# LED_Driver_-_4.net
KiCad netlist of a schematic drawn in Altium Designer
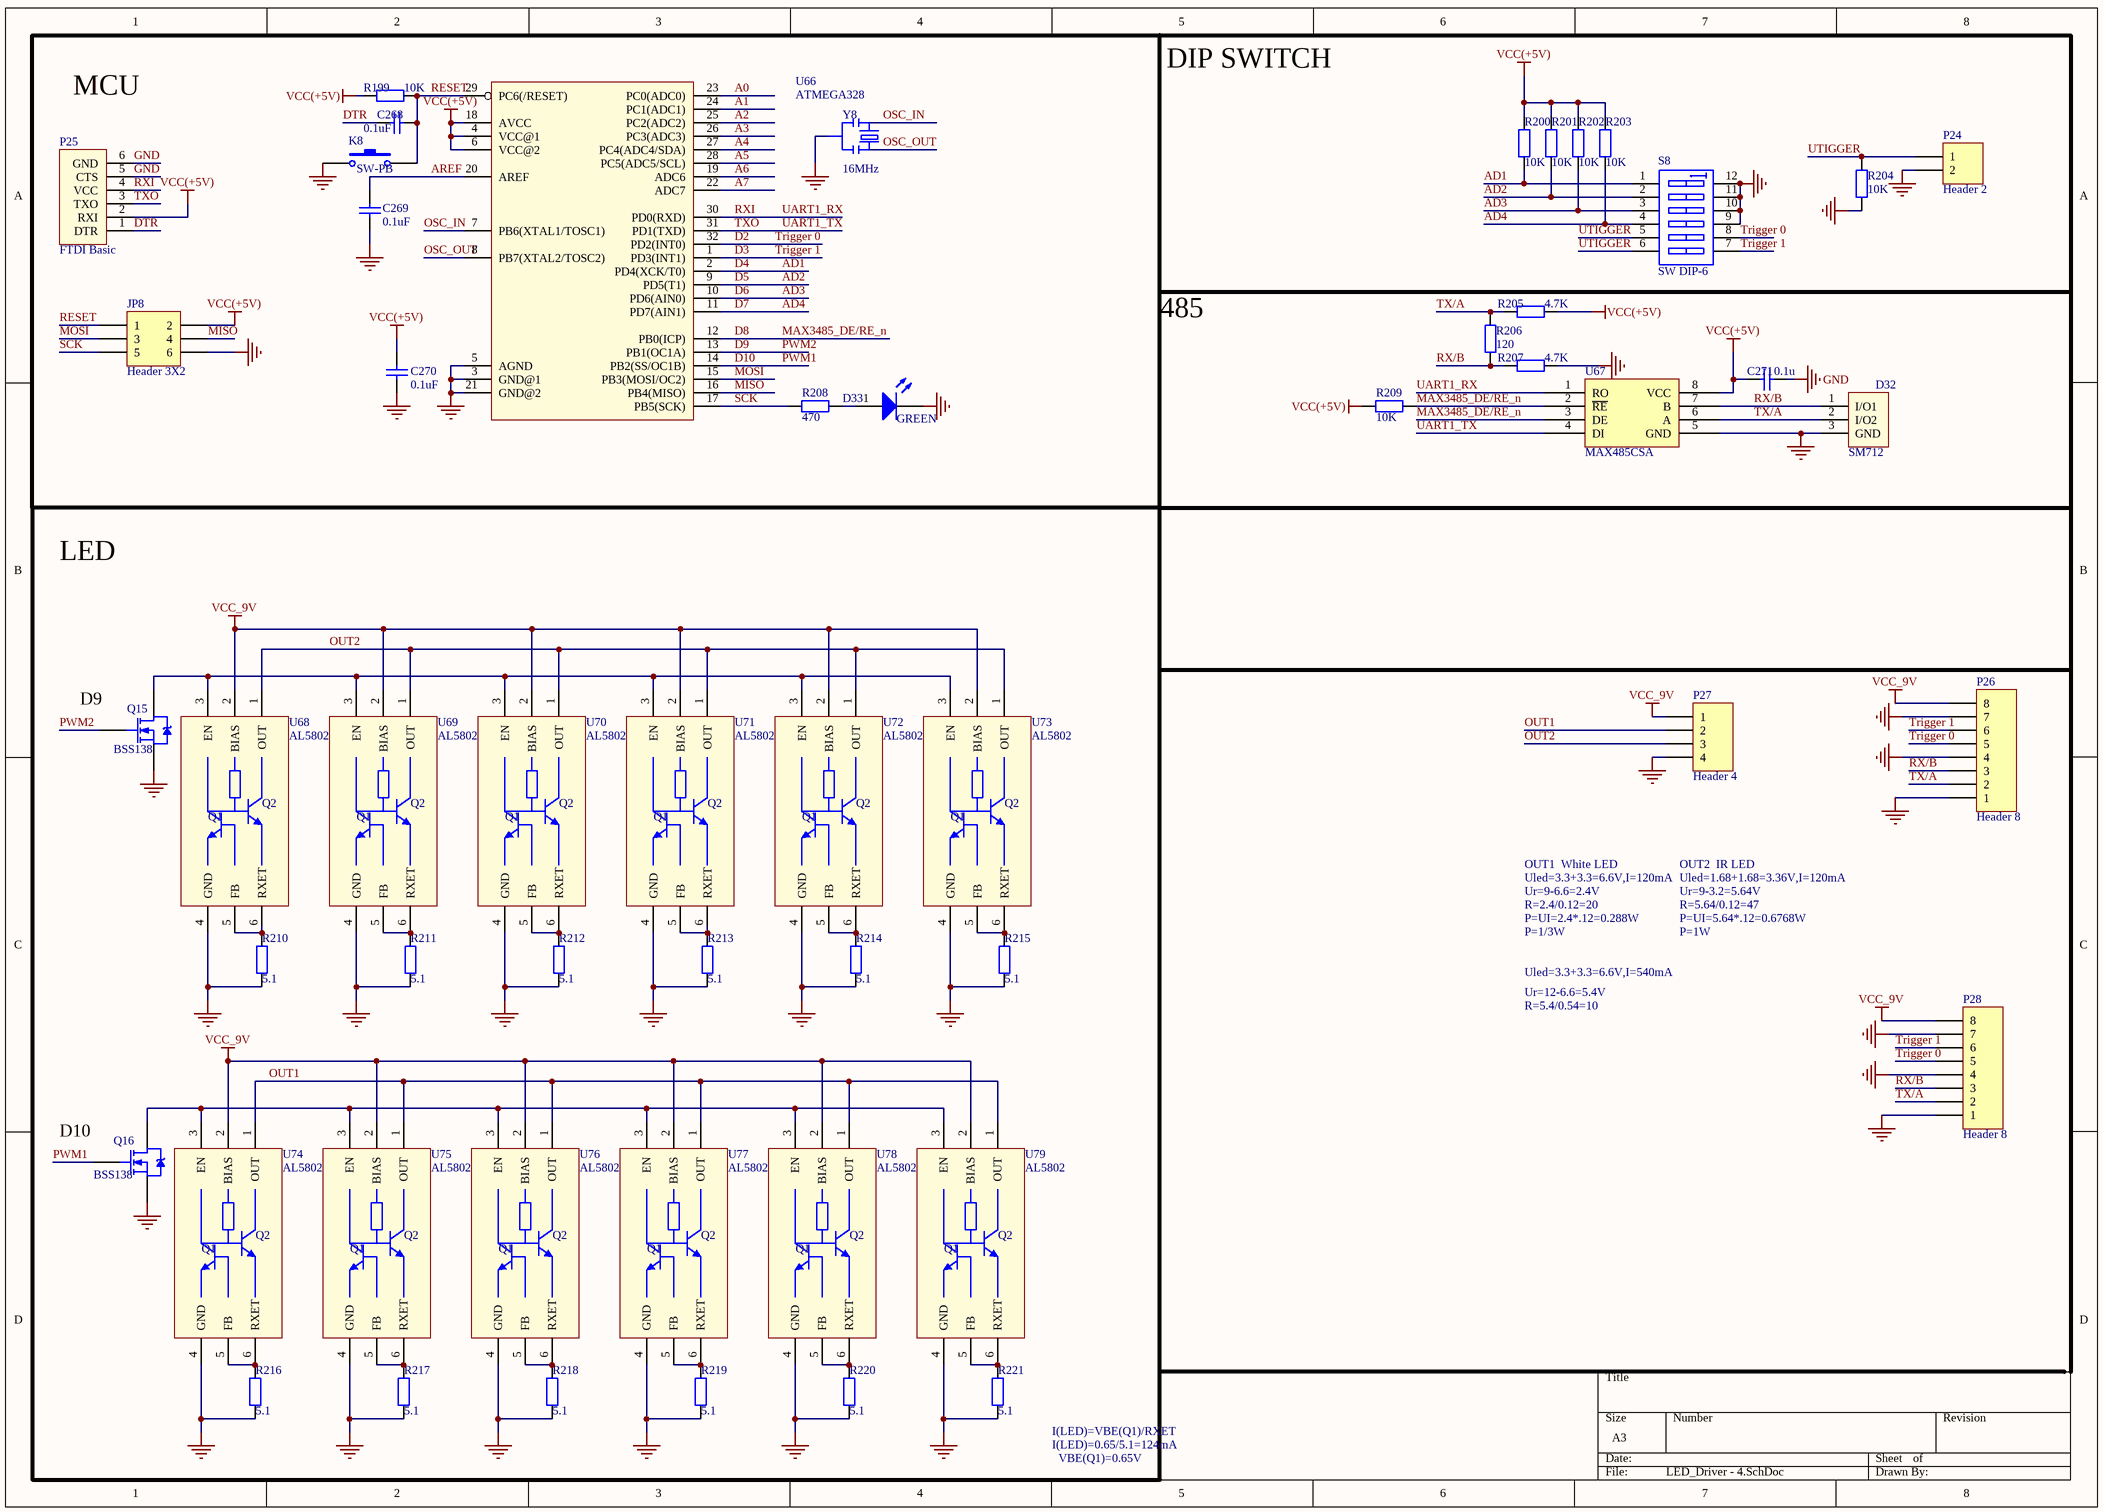
[diagram p0: LED_Driver - 4.SchDoc]

(export (version "E")
  (design (tool "Eeschema 10.0.6"))
  (components
    (comp (ref "C268")
      (value "0.1uF")
      (footprint "C0603")
      (description "Capacitor")
      (fields (field (name "IPARTNUMBER") "C100nF25V10%X7R") (field (name "VOLTAGE") "25V"))
      (libsource (lib "Schlib1") (part "CAP SMT C100nF25V10%X7R"))
    )
    (comp (ref "C269")
      (value "0.1uF")
      (footprint "C0603")
      (description "Capacitor")
      (fields (field (name "IPARTNUMBER") "C100nF25V10%X7R") (field (name "VOLTAGE") "25V"))
      (libsource (lib "Schlib1") (part "CAP SMT C100nF25V10%X7R"))
    )
    (comp (ref "C270")
      (value "0.1uF")
      (footprint "C0603")
      (description "Capacitor")
      (fields (field (name "IPARTNUMBER") "C100nF25V10%X7R") (field (name "VOLTAGE") "25V"))
      (libsource (lib "Schlib1") (part "CAP SMT C100nF25V10%X7R"))
    )
    (comp (ref "C271")
      (value "0.1u")
      (footprint "C0603")
      (description "Capacitor")
      (fields (field (name "PUBLISHER") "Altium Limited"))
      (libsource (lib "Miscellaneous Devices") (part "Cap"))
    )
    (comp (ref "D32")
      (value "SM712")
      (footprint "SOT23-3")
      (libsource (lib "STM32F4_CAM V2.0") (part "SM712"))
    )
    (comp (ref "D33")
      (value "GREEN")
      (footprint "LED0805")
      (description "Typical INFRARED GaAs LED")
      (fields (field (name "PUBLISHER") "Altium Limited"))
      (libsource (lib "DM642") (part "LED0"))
    )
    (comp (ref "JP8")
      (value "Header 3X2")
      (footprint "MHDR1X6")
      (description "Header, 3-Pin, Dual row")
      (fields (field (name "PUBLISHER") "Altium Limited"))
      (libsource (lib "Miscellaneous Connectors") (part "Header 3X2"))
    )
    (comp (ref "K8")
      (value "SW-PB")
      (footprint "157SW")
      (description "Switch")
      (fields (field (name "PUBLISHER") "Altium Limited"))
      (libsource (lib "Miscellaneous Devices") (part "SW-PB"))
    )
    (comp (ref "P24")
      (value "Header 2")
      (footprint "HDR1X2")
      (description "Header, 2-Pin")
      (fields (field (name "PUBLISHER") "Altium Limited"))
      (libsource (lib "Miscellaneous Connectors") (part "Header 2"))
    )
    (comp (ref "P25")
      (value "FTDI Basic")
      (footprint "MHDR1X6")
      (libsource (lib "PCB_Project1") (part "ARDUINO_SERIAL_PROGRAMPTH"))
    )
    (comp (ref "P26")
      (value "Header 8")
      (footprint "SH_1.25MM*8")
      (description "Header, 8-Pin")
      (fields (field (name "PUBLISHER") "Altium Limited"))
      (libsource (lib "Miscellaneous Connectors") (part "Header 8"))
    )
    (comp (ref "P27")
      (value "Header 4")
      (footprint "SMT_1.25MM*4")
      (description "Header, 4-Pin")
      (fields (field (name "PUBLISHER") "Altium Limited"))
      (libsource (lib "Miscellaneous Connectors") (part "Header 4"))
    )
    (comp (ref "P28")
      (value "Header 8")
      (footprint "SH_1.25MM*8")
      (description "Header, 8-Pin")
      (fields (field (name "PUBLISHER") "Altium Limited"))
      (libsource (lib "Miscellaneous Connectors") (part "Header 8"))
    )
    (comp (ref "Q15")
      (value "BSS138")
      (footprint "SOT-23 (Standard)")
      (fields
        (field (name "MANUFACTURER") "Fairchild Semiconductor")
        (field (name "MANUFACTURER PART NUMBER") "BSS123")
      )
      (libsource (lib "Miscellaneous_Devices") (part "NMOS"))
    )
    (comp (ref "Q16")
      (value "BSS138")
      (footprint "SOT-23 (Standard)")
      (fields
        (field (name "MANUFACTURER") "Fairchild Semiconductor")
        (field (name "MANUFACTURER PART NUMBER") "BSS123")
      )
      (libsource (lib "Miscellaneous_Devices") (part "NMOS"))
    )
    (comp (ref "R199")
      (value "10K")
      (footprint "R0603")
      (description "Resistor")
      (libsource (lib "") (part "Res2_2"))
    )
    (comp (ref "R200")
      (value "10K")
      (footprint "R0603")
      (description "Resistor")
      (libsource (lib "DM642") (part "Res2"))
    )
    (comp (ref "R201")
      (value "10K")
      (footprint "R0603")
      (description "Resistor")
      (libsource (lib "DM642") (part "Res2"))
    )
    (comp (ref "R202")
      (value "10K")
      (footprint "R0603")
      (description "Resistor")
      (libsource (lib "DM642") (part "Res2"))
    )
    (comp (ref "R203")
      (value "10K")
      (footprint "R0603")
      (description "Resistor")
      (libsource (lib "DM642") (part "Res2"))
    )
    (comp (ref "R204")
      (value "10K")
      (footprint "R0603")
      (description "Resistor")
      (fields (field (name "PUBLISHER") "Altium Limited"))
      (libsource (lib "Miscellaneous Devices") (part "Res2"))
    )
    (comp (ref "R205")
      (value "4.7K")
      (footprint "R0603")
      (description "Resistor")
      (libsource (lib "") (part "Res2_1"))
    )
    (comp (ref "R206")
      (value "120")
      (footprint "R0603")
      (description "Resistor")
      (libsource (lib "DM642") (part "Res2"))
    )
    (comp (ref "R207")
      (value "4.7K")
      (footprint "R0603")
      (description "Resistor")
      (libsource (lib "") (part "Res2_1"))
    )
    (comp (ref "R208")
      (value "470")
      (footprint "R0603")
      (description "Resistor")
      (libsource (lib "") (part "Res2_2"))
    )
    (comp (ref "R209")
      (value "10K")
      (footprint "R0603")
      (description "Resistor")
      (libsource (lib "") (part "Res2_1"))
    )
    (comp (ref "R210")
      (value "5.1")
      (footprint "R0603")
      (description "Resistor")
      (libsource (lib "DM642") (part "Res2"))
    )
    (comp (ref "R211")
      (value "5.1")
      (footprint "R0603")
      (description "Resistor")
      (libsource (lib "DM642") (part "Res2"))
    )
    (comp (ref "R212")
      (value "5.1")
      (footprint "R0603")
      (description "Resistor")
      (libsource (lib "DM642") (part "Res2"))
    )
    (comp (ref "R213")
      (value "5.1")
      (footprint "R0603")
      (description "Resistor")
      (libsource (lib "DM642") (part "Res2"))
    )
    (comp (ref "R214")
      (value "5.1")
      (footprint "R0603")
      (description "Resistor")
      (libsource (lib "DM642") (part "Res2"))
    )
    (comp (ref "R215")
      (value "5.1")
      (footprint "R0603")
      (description "Resistor")
      (libsource (lib "DM642") (part "Res2"))
    )
    (comp (ref "R216")
      (value "5.1")
      (footprint "R0603")
      (description "Resistor")
      (libsource (lib "DM642") (part "Res2"))
    )
    (comp (ref "R217")
      (value "5.1")
      (footprint "R0603")
      (description "Resistor")
      (libsource (lib "DM642") (part "Res2"))
    )
    (comp (ref "R218")
      (value "5.1")
      (footprint "R0603")
      (description "Resistor")
      (libsource (lib "DM642") (part "Res2"))
    )
    (comp (ref "R219")
      (value "5.1")
      (footprint "R0603")
      (description "Resistor")
      (libsource (lib "DM642") (part "Res2"))
    )
    (comp (ref "R220")
      (value "5.1")
      (footprint "R0603")
      (description "Resistor")
      (libsource (lib "DM642") (part "Res2"))
    )
    (comp (ref "R221")
      (value "5.1")
      (footprint "R0603")
      (description "Resistor")
      (libsource (lib "DM642") (part "Res2"))
    )
    (comp (ref "S8")
      (value "SW DIP-6")
      (footprint "DIP_SW_6WAY_SMD")
      (description "DIP Switch, 6 Position, SPST")
      (fields (field (name "PUBLISHER") "Altium Limited"))
      (libsource (lib "Miscellaneous Devices") (part "SW DIP-6"))
    )
    (comp (ref "U66")
      (value "ATMEGA328")
      (footprint "TQFP32-08")
      (libsource (lib "PCB_Project1") (part "ATMEGA168"))
    )
    (comp (ref "U67")
      (value "MAX485CSA")
      (footprint "SOIC-8")
      (libsource (lib "STM32F4_CAM V1.2") (part "MAX3485CSA"))
    )
    (comp (ref "U68") (value "AL5802") (footprint "SOT26") (libsource (lib "LED") (part "AL5802")))
    (comp (ref "U69") (value "AL5802") (footprint "SOT26") (libsource (lib "LED") (part "AL5802")))
    (comp (ref "U70") (value "AL5802") (footprint "SOT26") (libsource (lib "LED") (part "AL5802")))
    (comp (ref "U71") (value "AL5802") (footprint "SOT26") (libsource (lib "LED") (part "AL5802")))
    (comp (ref "U72") (value "AL5802") (footprint "SOT26") (libsource (lib "LED") (part "AL5802")))
    (comp (ref "U73") (value "AL5802") (footprint "SOT26") (libsource (lib "LED") (part "AL5802")))
    (comp (ref "U74") (value "AL5802") (footprint "SOT26") (libsource (lib "LED") (part "AL5802")))
    (comp (ref "U75") (value "AL5802") (footprint "SOT26") (libsource (lib "LED") (part "AL5802")))
    (comp (ref "U76") (value "AL5802") (footprint "SOT26") (libsource (lib "LED") (part "AL5802")))
    (comp (ref "U77") (value "AL5802") (footprint "SOT26") (libsource (lib "LED") (part "AL5802")))
    (comp (ref "U78") (value "AL5802") (footprint "SOT26") (libsource (lib "LED") (part "AL5802")))
    (comp (ref "U79") (value "AL5802") (footprint "SOT26") (libsource (lib "LED") (part "AL5802")))
    (comp (ref "Y8")
      (value "16MHz")
      (footprint "RESONATOR-SMD")
      (libsource (lib "SparkFun") (part "RESONATORSMD"))
    )
  )
  (nets
    (net (code "1") (name "/A0") (class "Default")
      (node (ref "U66") (pin "23") (pinfunction "PC0(ADC0)_23") (pintype "passive"))
    )
    (net (code "2") (name "/A1") (class "Default")
      (node (ref "U66") (pin "24") (pinfunction "PC1(ADC1)_24") (pintype "passive"))
    )
    (net (code "3") (name "/A2") (class "Default")
      (node (ref "U66") (pin "25") (pinfunction "PC2(ADC2)_25") (pintype "passive"))
    )
    (net (code "4") (name "/A3") (class "Default")
      (node (ref "U66") (pin "26") (pinfunction "PC3(ADC3)_26") (pintype "passive"))
    )
    (net (code "5") (name "/A4") (class "Default")
      (node (ref "U66") (pin "27") (pinfunction "PC4(ADC4/SDA)_27") (pintype "passive"))
    )
    (net (code "6") (name "/A5") (class "Default")
      (node (ref "U66") (pin "28") (pinfunction "PC5(ADC5/SCL)_28") (pintype "passive"))
    )
    (net (code "7") (name "/A6") (class "Default")
      (node (ref "U66") (pin "19") (pinfunction "ADC6_19") (pintype "passive"))
    )
    (net (code "8") (name "/A7") (class "Default")
      (node (ref "U66") (pin "22") (pinfunction "ADC7_22") (pintype "passive"))
    )
    (net (code "9") (name "/AD1") (class "Default")
      (node (ref "R200") (pin "2") (pinfunction "2_2") (pintype "passive"))
      (node (ref "S8") (pin "1") (pinfunction "A1_1") (pintype "passive"))
      (node (ref "U66") (pin "2") (pinfunction "PD4(XCK/T0)_2") (pintype "passive"))
    )
    (net (code "10") (name "/AD2") (class "Default")
      (node (ref "R201") (pin "2") (pinfunction "2_2") (pintype "passive"))
      (node (ref "S8") (pin "2") (pinfunction "A2_2") (pintype "passive"))
      (node (ref "U66") (pin "9") (pinfunction "PD5(T1)_9") (pintype "passive"))
    )
    (net (code "11") (name "/AD3") (class "Default")
      (node (ref "R202") (pin "2") (pinfunction "2_2") (pintype "passive"))
      (node (ref "S8") (pin "3") (pinfunction "A3_3") (pintype "passive"))
      (node (ref "U66") (pin "10") (pinfunction "PD6(AIN0)_10") (pintype "passive"))
    )
    (net (code "12") (name "/AD4") (class "Default")
      (node (ref "R203") (pin "2") (pinfunction "2_2") (pintype "passive"))
      (node (ref "S8") (pin "4") (pinfunction "A4_4") (pintype "passive"))
      (node (ref "U66") (pin "11") (pinfunction "PD7(AIN1)_11") (pintype "passive"))
    )
    (net (code "13") (name "/AREF") (class "Default")
      (node (ref "C269") (pin "2") (pinfunction "2_2") (pintype "passive"))
      (node (ref "U66") (pin "20") (pinfunction "AREF_20") (pintype "passive"))
    )
    (net (code "14") (name "/D2") (class "Default")
      (node (ref "P26") (pin "5") (pinfunction "5_5") (pintype "passive"))
      (node (ref "P28") (pin "5") (pinfunction "5_5") (pintype "passive"))
      (node (ref "S8") (pin "8") (pinfunction "B5_8") (pintype "passive"))
      (node (ref "U66") (pin "32") (pinfunction "PD2(INT0)_32") (pintype "passive"))
    )
    (net (code "15") (name "/D3") (class "Default")
      (node (ref "P26") (pin "6") (pinfunction "6_6") (pintype "passive"))
      (node (ref "P28") (pin "6") (pinfunction "6_6") (pintype "passive"))
      (node (ref "S8") (pin "7") (pinfunction "B6_7") (pintype "passive"))
      (node (ref "U66") (pin "1") (pinfunction "PD3(INT1)_1") (pintype "passive"))
    )
    (net (code "16") (name "/D8") (class "Default")
      (node (ref "R209") (pin "1") (pinfunction "1_1") (pintype "passive"))
      (node (ref "U66") (pin "12") (pinfunction "PB0(ICP)_12") (pintype "passive"))
      (node (ref "U67") (pin "2") (pinfunction "~{RE}_2") (pintype "passive"))
      (node (ref "U67") (pin "3") (pinfunction "DE_3") (pintype "passive"))
    )
    (net (code "17") (name "/D9") (class "Default")
      (node (ref "Q15") (pin "G") (pinfunction "G_G") (pintype "passive"))
      (node (ref "U66") (pin "13") (pinfunction "PB1(OC1A)_13") (pintype "passive"))
    )
    (net (code "18") (name "/D10") (class "Default")
      (node (ref "Q16") (pin "G") (pinfunction "G_G") (pintype "passive"))
      (node (ref "U66") (pin "14") (pinfunction "PB2(SS/OC1B)_14") (pintype "passive"))
    )
    (net (code "19") (name "/DTR") (class "Default")
      (node (ref "C268") (pin "1") (pinfunction "1_1") (pintype "passive"))
      (node (ref "P25") (pin "1") (pinfunction "DTR_1") (pintype "passive"))
    )
    (net (code "20") (name "/MISO") (class "Default")
      (node (ref "JP8") (pin "4") (pinfunction "4_4") (pintype "passive"))
      (node (ref "U66") (pin "16") (pinfunction "PB4(MISO)_16") (pintype "passive"))
    )
    (net (code "21") (name "/MOSI") (class "Default")
      (node (ref "JP8") (pin "3") (pinfunction "3_3") (pintype "passive"))
      (node (ref "U66") (pin "15") (pinfunction "PB3(MOSI/OC2)_15") (pintype "passive"))
    )
    (net (code "22") (name "/OSC_IN") (class "Default")
      (node (ref "U66") (pin "7") (pinfunction "PB6(XTAL1/TOSC1)_7") (pintype "passive"))
      (node (ref "Y8") (pin "3") (pinfunction "3_3") (pintype "passive"))
    )
    (net (code "23") (name "/OSC_OUT") (class "Default")
      (node (ref "U66") (pin "8") (pinfunction "PB7(XTAL2/TOSC2)_8") (pintype "passive"))
      (node (ref "Y8") (pin "1") (pinfunction "1_1") (pintype "passive"))
    )
    (net (code "24") (name "/OUT1") (class "Default")
      (node (ref "P27") (pin "2") (pinfunction "2_2") (pintype "passive"))
      (node (ref "U74") (pin "1") (pinfunction "OUT_1") (pintype "passive"))
      (node (ref "U75") (pin "1") (pinfunction "OUT_1") (pintype "passive"))
      (node (ref "U76") (pin "1") (pinfunction "OUT_1") (pintype "passive"))
      (node (ref "U77") (pin "1") (pinfunction "OUT_1") (pintype "passive"))
      (node (ref "U78") (pin "1") (pinfunction "OUT_1") (pintype "passive"))
      (node (ref "U79") (pin "1") (pinfunction "OUT_1") (pintype "passive"))
    )
    (net (code "25") (name "/OUT2") (class "Default")
      (node (ref "P27") (pin "3") (pinfunction "3_3") (pintype "passive"))
      (node (ref "U68") (pin "1") (pinfunction "OUT_1") (pintype "passive"))
      (node (ref "U69") (pin "1") (pinfunction "OUT_1") (pintype "passive"))
      (node (ref "U70") (pin "1") (pinfunction "OUT_1") (pintype "passive"))
      (node (ref "U71") (pin "1") (pinfunction "OUT_1") (pintype "passive"))
      (node (ref "U72") (pin "1") (pinfunction "OUT_1") (pintype "passive"))
      (node (ref "U73") (pin "1") (pinfunction "OUT_1") (pintype "passive"))
    )
    (net (code "26") (name "/RESET") (class "Default")
      (node (ref "C268") (pin "2") (pinfunction "2_2") (pintype "passive"))
      (node (ref "JP8") (pin "1") (pinfunction "1_1") (pintype "passive"))
      (node (ref "K8") (pin "2") (pinfunction "2_2") (pintype "passive"))
      (node (ref "R199") (pin "2") (pinfunction "2_2") (pintype "passive"))
      (node (ref "U66") (pin "29") (pinfunction "PC6(/RESET)_29") (pintype "passive"))
    )
    (net (code "27") (name "/RXI") (class "Default")
      (node (ref "P25") (pin "4") (pinfunction "VCC_4") (pintype "passive"))
      (node (ref "U66") (pin "30") (pinfunction "PD0(RXD)_30") (pintype "passive"))
      (node (ref "U67") (pin "1") (pinfunction "RO_1") (pintype "passive"))
    )
    (net (code "28") (name "/RX{slash}B") (class "Default")
      (node (ref "D32") (pin "1") (pinfunction "I/O1_1") (pintype "passive"))
      (node (ref "P26") (pin "3") (pinfunction "3_3") (pintype "passive"))
      (node (ref "P28") (pin "3") (pinfunction "3_3") (pintype "passive"))
      (node (ref "R206") (pin "2") (pinfunction "2_2") (pintype "passive"))
      (node (ref "R207") (pin "2") (pinfunction "2_2") (pintype "passive"))
      (node (ref "U67") (pin "7") (pinfunction "B_7") (pintype "passive"))
    )
    (net (code "29") (name "/SCK") (class "Default")
      (node (ref "JP8") (pin "5") (pinfunction "5_5") (pintype "passive"))
      (node (ref "R208") (pin "1") (pinfunction "1_1") (pintype "passive"))
      (node (ref "U66") (pin "17") (pinfunction "PB5(SCK)_17") (pintype "passive"))
    )
    (net (code "30") (name "/TXO") (class "Default")
      (node (ref "P25") (pin "3") (pinfunction "TXO_3") (pintype "passive"))
      (node (ref "U66") (pin "31") (pinfunction "PD1(TXD)_31") (pintype "passive"))
      (node (ref "U67") (pin "4") (pinfunction "DI_4") (pintype "passive"))
    )
    (net (code "31") (name "/TX{slash}A") (class "Default")
      (node (ref "D32") (pin "2") (pinfunction "I/O2_2") (pintype "passive"))
      (node (ref "P26") (pin "2") (pinfunction "2_2") (pintype "passive"))
      (node (ref "P28") (pin "2") (pinfunction "2_2") (pintype "passive"))
      (node (ref "R205") (pin "2") (pinfunction "2_2") (pintype "passive"))
      (node (ref "R206") (pin "1") (pinfunction "1_1") (pintype "passive"))
      (node (ref "U67") (pin "6") (pinfunction "A_6") (pintype "passive"))
    )
    (net (code "32") (name "/UTIGGER") (class "Default")
      (node (ref "P24") (pin "1") (pinfunction "1_1") (pintype "passive"))
      (node (ref "R204") (pin "2") (pinfunction "2_2") (pintype "passive"))
      (node (ref "S8") (pin "5") (pinfunction "A5_5") (pintype "passive"))
      (node (ref "S8") (pin "6") (pinfunction "A6_6") (pintype "passive"))
    )
    (net (code "33") (name "GND") (class "Default")
      (node (ref "C269") (pin "1") (pinfunction "1_1") (pintype "passive"))
      (node (ref "C270") (pin "2") (pinfunction "2_2") (pintype "passive"))
      (node (ref "C271") (pin "1") (pinfunction "1_1") (pintype "passive"))
      (node (ref "D32") (pin "3") (pinfunction "GND_3") (pintype "passive"))
      (node (ref "D33") (pin "2") (pinfunction "K_2") (pintype "passive"))
      (node (ref "JP8") (pin "6") (pinfunction "6_6") (pintype "passive"))
      (node (ref "K8") (pin "1") (pinfunction "1_1") (pintype "passive"))
      (node (ref "P24") (pin "2") (pinfunction "2_2") (pintype "passive"))
      (node (ref "P25") (pin "5") (pinfunction "CTS_5") (pintype "passive"))
      (node (ref "P25") (pin "6") (pinfunction "GND_6") (pintype "passive"))
      (node (ref "P26") (pin "1") (pinfunction "1_1") (pintype "passive"))
      (node (ref "P26") (pin "4") (pinfunction "4_4") (pintype "passive"))
      (node (ref "P26") (pin "7") (pinfunction "7_7") (pintype "passive"))
      (node (ref "P27") (pin "4") (pinfunction "4_4") (pintype "passive"))
      (node (ref "P28") (pin "1") (pinfunction "1_1") (pintype "passive"))
      (node (ref "P28") (pin "4") (pinfunction "4_4") (pintype "passive"))
      (node (ref "P28") (pin "7") (pinfunction "7_7") (pintype "passive"))
      (node (ref "Q15") (pin "S") (pinfunction "S_S") (pintype "passive"))
      (node (ref "Q16") (pin "S") (pinfunction "S_S") (pintype "passive"))
      (node (ref "R204") (pin "1") (pinfunction "1_1") (pintype "passive"))
      (node (ref "R207") (pin "1") (pinfunction "1_1") (pintype "passive"))
      (node (ref "R210") (pin "2") (pinfunction "2_2") (pintype "passive"))
      (node (ref "R211") (pin "2") (pinfunction "2_2") (pintype "passive"))
      (node (ref "R212") (pin "2") (pinfunction "2_2") (pintype "passive"))
      (node (ref "R213") (pin "2") (pinfunction "2_2") (pintype "passive"))
      (node (ref "R214") (pin "2") (pinfunction "2_2") (pintype "passive"))
      (node (ref "R215") (pin "2") (pinfunction "2_2") (pintype "passive"))
      (node (ref "R216") (pin "2") (pinfunction "2_2") (pintype "passive"))
      (node (ref "R217") (pin "2") (pinfunction "2_2") (pintype "passive"))
      (node (ref "R218") (pin "2") (pinfunction "2_2") (pintype "passive"))
      (node (ref "R219") (pin "2") (pinfunction "2_2") (pintype "passive"))
      (node (ref "R220") (pin "2") (pinfunction "2_2") (pintype "passive"))
      (node (ref "R221") (pin "2") (pinfunction "2_2") (pintype "passive"))
      (node (ref "S8") (pin "10") (pinfunction "B3_10") (pintype "passive"))
      (node (ref "S8") (pin "11") (pinfunction "B2_11") (pintype "passive"))
      (node (ref "S8") (pin "12") (pinfunction "B1_12") (pintype "passive"))
      (node (ref "S8") (pin "9") (pinfunction "B4_9") (pintype "passive"))
      (node (ref "U66") (pin "21") (pinfunction "GND@2_21") (pintype "passive"))
      (node (ref "U66") (pin "3") (pinfunction "GND@1_3") (pintype "passive"))
      (node (ref "U66") (pin "5") (pinfunction "AGND_5") (pintype "passive"))
      (node (ref "U67") (pin "5") (pinfunction "GND_5") (pintype "passive"))
      (node (ref "U68") (pin "4") (pinfunction "GND_4") (pintype "passive"))
      (node (ref "U69") (pin "4") (pinfunction "GND_4") (pintype "passive"))
      (node (ref "U70") (pin "4") (pinfunction "GND_4") (pintype "passive"))
      (node (ref "U71") (pin "4") (pinfunction "GND_4") (pintype "passive"))
      (node (ref "U72") (pin "4") (pinfunction "GND_4") (pintype "passive"))
      (node (ref "U73") (pin "4") (pinfunction "GND_4") (pintype "passive"))
      (node (ref "U74") (pin "4") (pinfunction "GND_4") (pintype "passive"))
      (node (ref "U75") (pin "4") (pinfunction "GND_4") (pintype "passive"))
      (node (ref "U76") (pin "4") (pinfunction "GND_4") (pintype "passive"))
      (node (ref "U77") (pin "4") (pinfunction "GND_4") (pintype "passive"))
      (node (ref "U78") (pin "4") (pinfunction "GND_4") (pintype "passive"))
      (node (ref "U79") (pin "4") (pinfunction "GND_4") (pintype "passive"))
      (node (ref "Y8") (pin "2") (pinfunction "2_2") (pintype "passive"))
    )
    (net (code "34") (name "Net-(D33-A)") (class "Default")
      (node (ref "D33") (pin "1") (pinfunction "A_1") (pintype "passive"))
      (node (ref "R208") (pin "2") (pinfunction "2_2") (pintype "passive"))
    )
    (net (code "35") (name "Net-(U68-EN)") (class "Default")
      (node (ref "Q15") (pin "D") (pinfunction "D_D") (pintype "passive"))
      (node (ref "U68") (pin "3") (pinfunction "EN_3") (pintype "passive"))
      (node (ref "U69") (pin "3") (pinfunction "EN_3") (pintype "passive"))
      (node (ref "U70") (pin "3") (pinfunction "EN_3") (pintype "passive"))
      (node (ref "U71") (pin "3") (pinfunction "EN_3") (pintype "passive"))
      (node (ref "U72") (pin "3") (pinfunction "EN_3") (pintype "passive"))
      (node (ref "U73") (pin "3") (pinfunction "EN_3") (pintype "passive"))
    )
    (net (code "36") (name "Net-(U68-FB)") (class "Default")
      (node (ref "R210") (pin "1") (pinfunction "1_1") (pintype "passive"))
      (node (ref "U68") (pin "5") (pinfunction "FB_5") (pintype "passive"))
      (node (ref "U68") (pin "6") (pinfunction "RXET_6") (pintype "passive"))
    )
    (net (code "37") (name "Net-(U69-FB)") (class "Default")
      (node (ref "R211") (pin "1") (pinfunction "1_1") (pintype "passive"))
      (node (ref "U69") (pin "5") (pinfunction "FB_5") (pintype "passive"))
      (node (ref "U69") (pin "6") (pinfunction "RXET_6") (pintype "passive"))
    )
    (net (code "38") (name "Net-(U70-FB)") (class "Default")
      (node (ref "R212") (pin "1") (pinfunction "1_1") (pintype "passive"))
      (node (ref "U70") (pin "5") (pinfunction "FB_5") (pintype "passive"))
      (node (ref "U70") (pin "6") (pinfunction "RXET_6") (pintype "passive"))
    )
    (net (code "39") (name "Net-(U71-FB)") (class "Default")
      (node (ref "R213") (pin "1") (pinfunction "1_1") (pintype "passive"))
      (node (ref "U71") (pin "5") (pinfunction "FB_5") (pintype "passive"))
      (node (ref "U71") (pin "6") (pinfunction "RXET_6") (pintype "passive"))
    )
    (net (code "40") (name "Net-(U72-FB)") (class "Default")
      (node (ref "R214") (pin "1") (pinfunction "1_1") (pintype "passive"))
      (node (ref "U72") (pin "5") (pinfunction "FB_5") (pintype "passive"))
      (node (ref "U72") (pin "6") (pinfunction "RXET_6") (pintype "passive"))
    )
    (net (code "41") (name "Net-(U73-FB)") (class "Default")
      (node (ref "R215") (pin "1") (pinfunction "1_1") (pintype "passive"))
      (node (ref "U73") (pin "5") (pinfunction "FB_5") (pintype "passive"))
      (node (ref "U73") (pin "6") (pinfunction "RXET_6") (pintype "passive"))
    )
    (net (code "42") (name "Net-(U74-EN)") (class "Default")
      (node (ref "Q16") (pin "D") (pinfunction "D_D") (pintype "passive"))
      (node (ref "U74") (pin "3") (pinfunction "EN_3") (pintype "passive"))
      (node (ref "U75") (pin "3") (pinfunction "EN_3") (pintype "passive"))
      (node (ref "U76") (pin "3") (pinfunction "EN_3") (pintype "passive"))
      (node (ref "U77") (pin "3") (pinfunction "EN_3") (pintype "passive"))
      (node (ref "U78") (pin "3") (pinfunction "EN_3") (pintype "passive"))
      (node (ref "U79") (pin "3") (pinfunction "EN_3") (pintype "passive"))
    )
    (net (code "43") (name "Net-(U74-FB)") (class "Default")
      (node (ref "R216") (pin "1") (pinfunction "1_1") (pintype "passive"))
      (node (ref "U74") (pin "5") (pinfunction "FB_5") (pintype "passive"))
      (node (ref "U74") (pin "6") (pinfunction "RXET_6") (pintype "passive"))
    )
    (net (code "44") (name "Net-(U75-FB)") (class "Default")
      (node (ref "R217") (pin "1") (pinfunction "1_1") (pintype "passive"))
      (node (ref "U75") (pin "5") (pinfunction "FB_5") (pintype "passive"))
      (node (ref "U75") (pin "6") (pinfunction "RXET_6") (pintype "passive"))
    )
    (net (code "45") (name "Net-(U76-FB)") (class "Default")
      (node (ref "R218") (pin "1") (pinfunction "1_1") (pintype "passive"))
      (node (ref "U76") (pin "5") (pinfunction "FB_5") (pintype "passive"))
      (node (ref "U76") (pin "6") (pinfunction "RXET_6") (pintype "passive"))
    )
    (net (code "46") (name "Net-(U77-FB)") (class "Default")
      (node (ref "R219") (pin "1") (pinfunction "1_1") (pintype "passive"))
      (node (ref "U77") (pin "5") (pinfunction "FB_5") (pintype "passive"))
      (node (ref "U77") (pin "6") (pinfunction "RXET_6") (pintype "passive"))
    )
    (net (code "47") (name "Net-(U78-FB)") (class "Default")
      (node (ref "R220") (pin "1") (pinfunction "1_1") (pintype "passive"))
      (node (ref "U78") (pin "5") (pinfunction "FB_5") (pintype "passive"))
      (node (ref "U78") (pin "6") (pinfunction "RXET_6") (pintype "passive"))
    )
    (net (code "48") (name "Net-(U79-FB)") (class "Default")
      (node (ref "R221") (pin "1") (pinfunction "1_1") (pintype "passive"))
      (node (ref "U79") (pin "5") (pinfunction "FB_5") (pintype "passive"))
      (node (ref "U79") (pin "6") (pinfunction "RXET_6") (pintype "passive"))
    )
    (net (code "49") (name "VCC(+5V)") (class "Default")
      (node (ref "C270") (pin "1") (pinfunction "1_1") (pintype "passive"))
      (node (ref "C271") (pin "2") (pinfunction "2_2") (pintype "passive"))
      (node (ref "JP8") (pin "2") (pinfunction "2_2") (pintype "passive"))
      (node (ref "P25") (pin "2") (pinfunction "RXI_2") (pintype "passive"))
      (node (ref "R199") (pin "1") (pinfunction "1_1") (pintype "passive"))
      (node (ref "R200") (pin "1") (pinfunction "1_1") (pintype "passive"))
      (node (ref "R201") (pin "1") (pinfunction "1_1") (pintype "passive"))
      (node (ref "R202") (pin "1") (pinfunction "1_1") (pintype "passive"))
      (node (ref "R203") (pin "1") (pinfunction "1_1") (pintype "passive"))
      (node (ref "R205") (pin "1") (pinfunction "1_1") (pintype "passive"))
      (node (ref "R209") (pin "2") (pinfunction "2_2") (pintype "passive"))
      (node (ref "U66") (pin "18") (pinfunction "AVCC_18") (pintype "passive"))
      (node (ref "U66") (pin "4") (pinfunction "VCC@1_4") (pintype "passive"))
      (node (ref "U66") (pin "6") (pinfunction "VCC@2_6") (pintype "passive"))
      (node (ref "U67") (pin "8") (pinfunction "VCC_8") (pintype "passive"))
    )
    (net (code "50") (name "VCC_9V") (class "Default")
      (node (ref "P26") (pin "8") (pinfunction "8_8") (pintype "passive"))
      (node (ref "P27") (pin "1") (pinfunction "1_1") (pintype "passive"))
      (node (ref "P28") (pin "8") (pinfunction "8_8") (pintype "passive"))
      (node (ref "U68") (pin "2") (pinfunction "BIAS_2") (pintype "passive"))
      (node (ref "U69") (pin "2") (pinfunction "BIAS_2") (pintype "passive"))
      (node (ref "U70") (pin "2") (pinfunction "BIAS_2") (pintype "passive"))
      (node (ref "U71") (pin "2") (pinfunction "BIAS_2") (pintype "passive"))
      (node (ref "U72") (pin "2") (pinfunction "BIAS_2") (pintype "passive"))
      (node (ref "U73") (pin "2") (pinfunction "BIAS_2") (pintype "passive"))
      (node (ref "U74") (pin "2") (pinfunction "BIAS_2") (pintype "passive"))
      (node (ref "U75") (pin "2") (pinfunction "BIAS_2") (pintype "passive"))
      (node (ref "U76") (pin "2") (pinfunction "BIAS_2") (pintype "passive"))
      (node (ref "U77") (pin "2") (pinfunction "BIAS_2") (pintype "passive"))
      (node (ref "U78") (pin "2") (pinfunction "BIAS_2") (pintype "passive"))
      (node (ref "U79") (pin "2") (pinfunction "BIAS_2") (pintype "passive"))
    )
  )
)
